# Precision_LPC.net
KiCad netlist of a schematic drawn in EAGLE
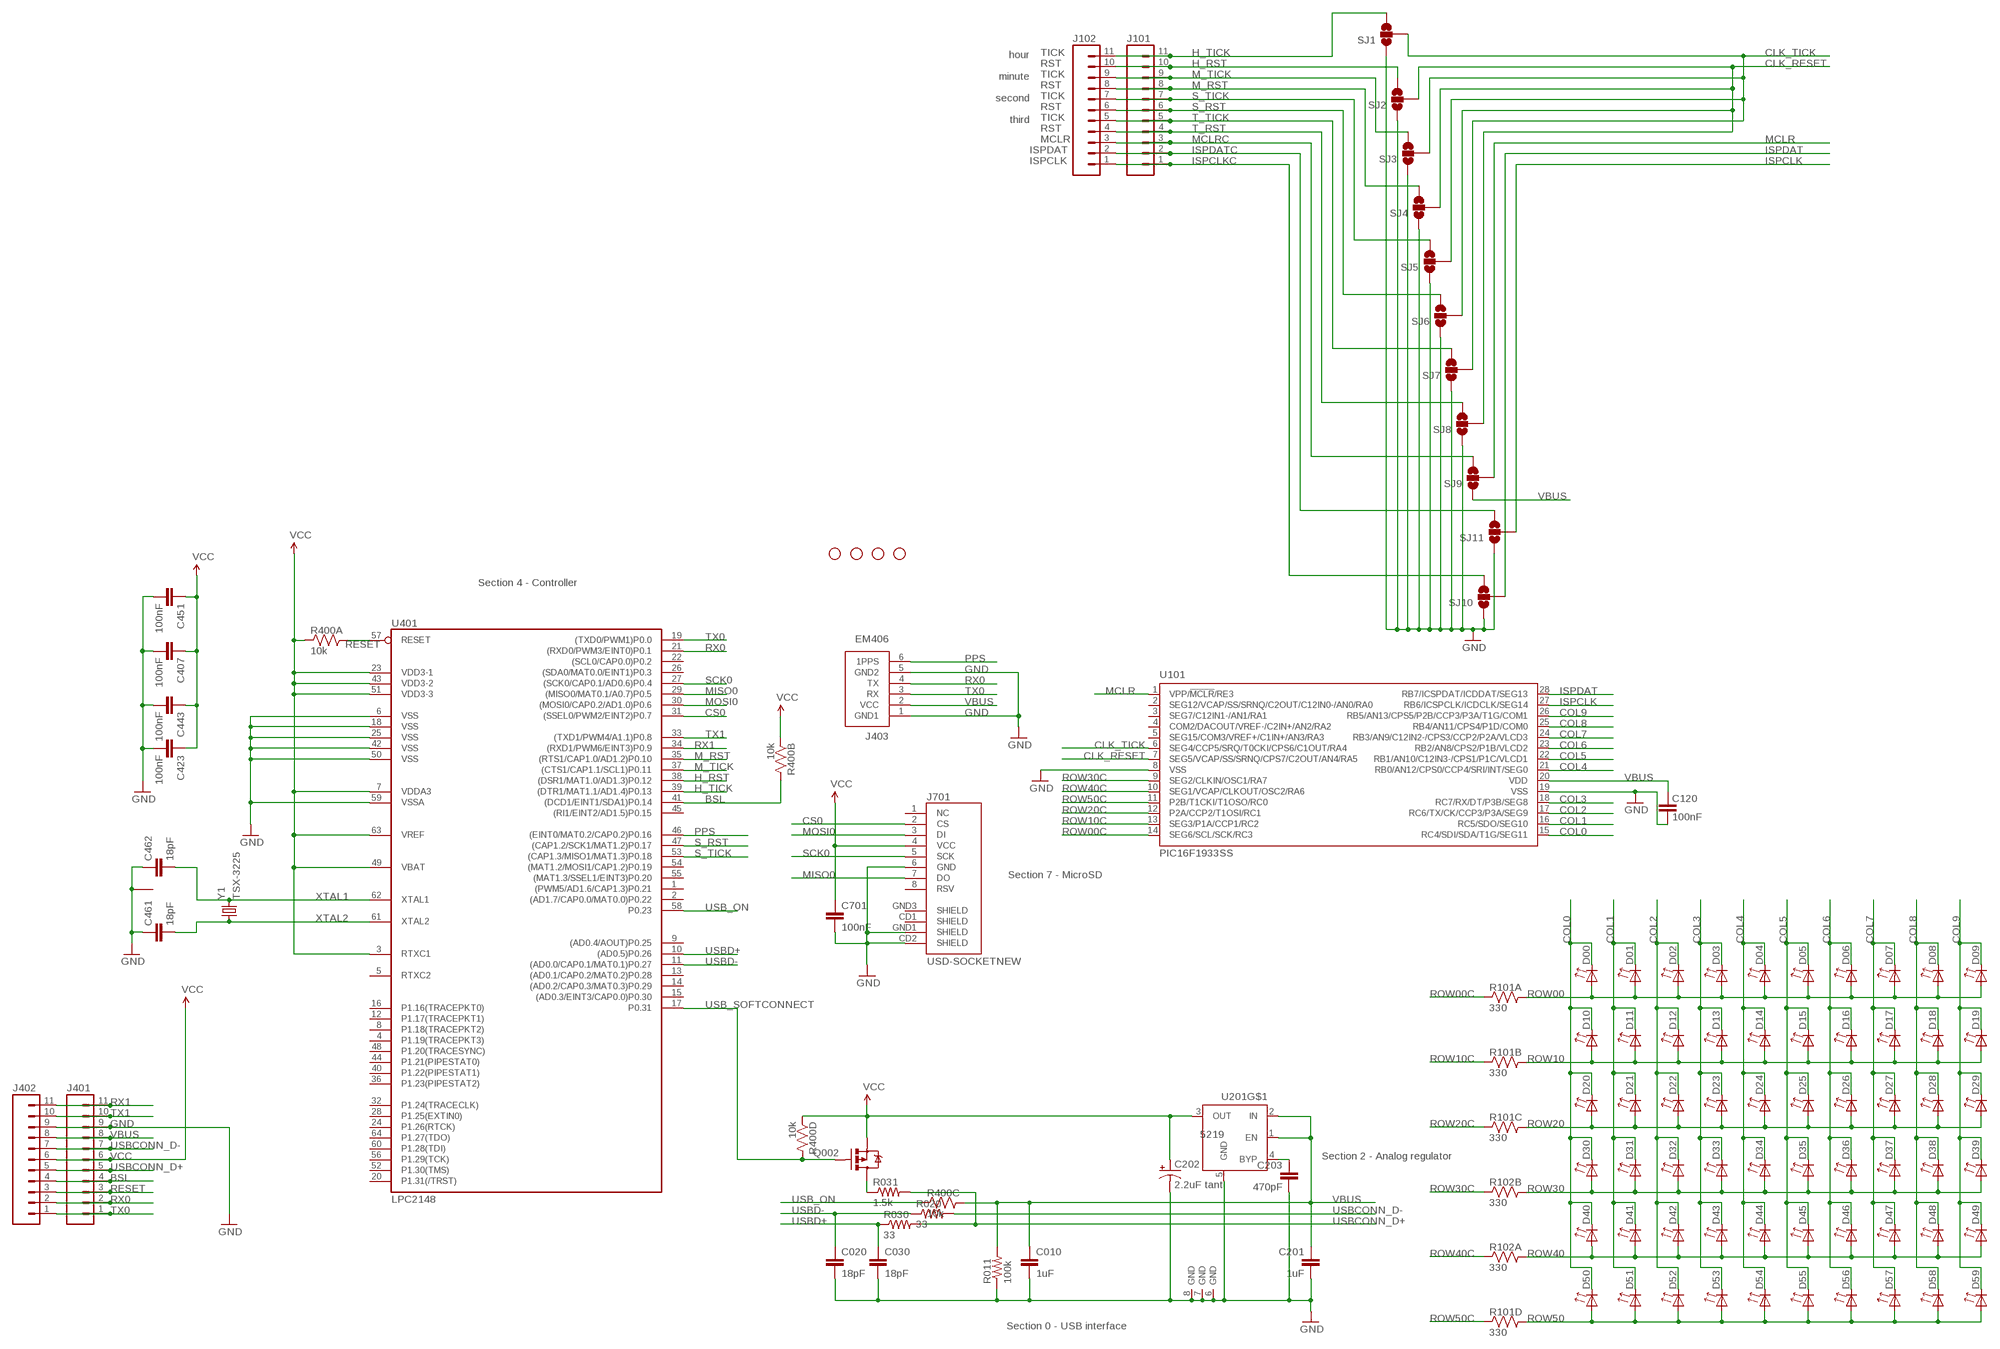
[diagram p0: schematic, sheet 1]

(export (version "E")
  (design (tool "Eeschema 10.0.6"))
  (components
    (comp (ref "C010")
      (value "1uF")
      (footprint "eagle-import:0402-CAP")
      (libsource (lib "eagle-import") (part "CAP0402-CAP"))
    )
    (comp (ref "C020")
      (value "18pF")
      (footprint "eagle-import:0402-CAP")
      (libsource (lib "eagle-import") (part "CAP0402-CAP"))
    )
    (comp (ref "C030")
      (value "18pF")
      (footprint "eagle-import:0402-CAP")
      (libsource (lib "eagle-import") (part "CAP0402-CAP"))
    )
    (comp (ref "C120")
      (value "100nF")
      (footprint "eagle-import:0402-CAP")
      (libsource (lib "eagle-import") (part "CAP0402-CAP"))
    )
    (comp (ref "C201")
      (value "1uF")
      (footprint "eagle-import:0402-CAP")
      (libsource (lib "eagle-import") (part "CAP0402-CAP"))
    )
    (comp (ref "C202")
      (value "2.2uF tant")
      (footprint "eagle-import:EIA3216")
      (libsource (lib "eagle-import") (part "CAP_POL1206"))
    )
    (comp (ref "C203")
      (value "470pF")
      (footprint "eagle-import:0402-CAP")
      (libsource (lib "eagle-import") (part "CAP0402-CAP"))
    )
    (comp (ref "C407")
      (value "100nF")
      (footprint "eagle-import:0402-CAP")
      (libsource (lib "eagle-import") (part "CAP0402-CAP"))
    )
    (comp (ref "C423")
      (value "100nF")
      (footprint "eagle-import:0402-CAP")
      (libsource (lib "eagle-import") (part "CAP0402-CAP"))
    )
    (comp (ref "C443")
      (value "100nF")
      (footprint "eagle-import:0402-CAP")
      (libsource (lib "eagle-import") (part "CAP0402-CAP"))
    )
    (comp (ref "C451")
      (value "100nF")
      (footprint "eagle-import:0402-CAP")
      (libsource (lib "eagle-import") (part "CAP0402-CAP"))
    )
    (comp (ref "C461")
      (value "18pF")
      (footprint "eagle-import:0402-CAP")
      (libsource (lib "eagle-import") (part "CAP0402-CAP"))
    )
    (comp (ref "C462")
      (value "18pF")
      (footprint "eagle-import:0402-CAP")
      (libsource (lib "eagle-import") (part "CAP0402-CAP"))
    )
    (comp (ref "C701")
      (value "100nF")
      (footprint "eagle-import:0402-CAP")
      (libsource (lib "eagle-import") (part "CAP0402-CAP"))
    )
    (comp (ref "D00")
      (value "LED0603_SIDE")
      (footprint "eagle-import:LED0603_SIDE")
      (libsource (lib "eagle-import") (part "LED0603_SIDE"))
    )
    (comp (ref "D01")
      (value "LED0603_SIDE")
      (footprint "eagle-import:LED0603_SIDE")
      (libsource (lib "eagle-import") (part "LED0603_SIDE"))
    )
    (comp (ref "D02")
      (value "LED0603_SIDE")
      (footprint "eagle-import:LED0603_SIDE")
      (libsource (lib "eagle-import") (part "LED0603_SIDE"))
    )
    (comp (ref "D03")
      (value "LED0603_SIDE")
      (footprint "eagle-import:LED0603_SIDE")
      (libsource (lib "eagle-import") (part "LED0603_SIDE"))
    )
    (comp (ref "D04")
      (value "LED0603_SIDE")
      (footprint "eagle-import:LED0603_SIDE")
      (libsource (lib "eagle-import") (part "LED0603_SIDE"))
    )
    (comp (ref "D05")
      (value "LED0603_SIDE")
      (footprint "eagle-import:LED0603_SIDE")
      (libsource (lib "eagle-import") (part "LED0603_SIDE"))
    )
    (comp (ref "D06")
      (value "LED0603_SIDE")
      (footprint "eagle-import:LED0603_SIDE")
      (libsource (lib "eagle-import") (part "LED0603_SIDE"))
    )
    (comp (ref "D07")
      (value "LED0603_SIDE")
      (footprint "eagle-import:LED0603_SIDE")
      (libsource (lib "eagle-import") (part "LED0603_SIDE"))
    )
    (comp (ref "D08")
      (value "LED0603_SIDE")
      (footprint "eagle-import:LED0603_SIDE")
      (libsource (lib "eagle-import") (part "LED0603_SIDE"))
    )
    (comp (ref "D09")
      (value "LED0603_SIDE")
      (footprint "eagle-import:LED0603_SIDE")
      (libsource (lib "eagle-import") (part "LED0603_SIDE"))
    )
    (comp (ref "D10")
      (value "LED0603_SIDE")
      (footprint "eagle-import:LED0603_SIDE")
      (libsource (lib "eagle-import") (part "LED0603_SIDE"))
    )
    (comp (ref "D11")
      (value "LED0603_SIDE")
      (footprint "eagle-import:LED0603_SIDE")
      (libsource (lib "eagle-import") (part "LED0603_SIDE"))
    )
    (comp (ref "D12")
      (value "LED0603_SIDE")
      (footprint "eagle-import:LED0603_SIDE")
      (libsource (lib "eagle-import") (part "LED0603_SIDE"))
    )
    (comp (ref "D13")
      (value "LED0603_SIDE")
      (footprint "eagle-import:LED0603_SIDE")
      (libsource (lib "eagle-import") (part "LED0603_SIDE"))
    )
    (comp (ref "D14")
      (value "LED0603_SIDE")
      (footprint "eagle-import:LED0603_SIDE")
      (libsource (lib "eagle-import") (part "LED0603_SIDE"))
    )
    (comp (ref "D15")
      (value "LED0603_SIDE")
      (footprint "eagle-import:LED0603_SIDE")
      (libsource (lib "eagle-import") (part "LED0603_SIDE"))
    )
    (comp (ref "D16")
      (value "LED0603_SIDE")
      (footprint "eagle-import:LED0603_SIDE")
      (libsource (lib "eagle-import") (part "LED0603_SIDE"))
    )
    (comp (ref "D17")
      (value "LED0603_SIDE")
      (footprint "eagle-import:LED0603_SIDE")
      (libsource (lib "eagle-import") (part "LED0603_SIDE"))
    )
    (comp (ref "D18")
      (value "LED0603_SIDE")
      (footprint "eagle-import:LED0603_SIDE")
      (libsource (lib "eagle-import") (part "LED0603_SIDE"))
    )
    (comp (ref "D19")
      (value "LED0603_SIDE")
      (footprint "eagle-import:LED0603_SIDE")
      (libsource (lib "eagle-import") (part "LED0603_SIDE"))
    )
    (comp (ref "D20")
      (value "LED0603_SIDE")
      (footprint "eagle-import:LED0603_SIDE")
      (libsource (lib "eagle-import") (part "LED0603_SIDE"))
    )
    (comp (ref "D21")
      (value "LED0603_SIDE")
      (footprint "eagle-import:LED0603_SIDE")
      (libsource (lib "eagle-import") (part "LED0603_SIDE"))
    )
    (comp (ref "D22")
      (value "LED0603_SIDE")
      (footprint "eagle-import:LED0603_SIDE")
      (libsource (lib "eagle-import") (part "LED0603_SIDE"))
    )
    (comp (ref "D23")
      (value "LED0603_SIDE")
      (footprint "eagle-import:LED0603_SIDE")
      (libsource (lib "eagle-import") (part "LED0603_SIDE"))
    )
    (comp (ref "D24")
      (value "LED0603_SIDE")
      (footprint "eagle-import:LED0603_SIDE")
      (libsource (lib "eagle-import") (part "LED0603_SIDE"))
    )
    (comp (ref "D25")
      (value "LED0603_SIDE")
      (footprint "eagle-import:LED0603_SIDE")
      (libsource (lib "eagle-import") (part "LED0603_SIDE"))
    )
    (comp (ref "D26")
      (value "LED0603_SIDE")
      (footprint "eagle-import:LED0603_SIDE")
      (libsource (lib "eagle-import") (part "LED0603_SIDE"))
    )
    (comp (ref "D27")
      (value "LED0603_SIDE")
      (footprint "eagle-import:LED0603_SIDE")
      (libsource (lib "eagle-import") (part "LED0603_SIDE"))
    )
    (comp (ref "D28")
      (value "LED0603_SIDE")
      (footprint "eagle-import:LED0603_SIDE")
      (libsource (lib "eagle-import") (part "LED0603_SIDE"))
    )
    (comp (ref "D29")
      (value "LED0603_SIDE")
      (footprint "eagle-import:LED0603_SIDE")
      (libsource (lib "eagle-import") (part "LED0603_SIDE"))
    )
    (comp (ref "D30")
      (value "LED0603_SIDE")
      (footprint "eagle-import:LED0603_SIDE")
      (libsource (lib "eagle-import") (part "LED0603_SIDE"))
    )
    (comp (ref "D31")
      (value "LED0603_SIDE")
      (footprint "eagle-import:LED0603_SIDE")
      (libsource (lib "eagle-import") (part "LED0603_SIDE"))
    )
    (comp (ref "D32")
      (value "LED0603_SIDE")
      (footprint "eagle-import:LED0603_SIDE")
      (libsource (lib "eagle-import") (part "LED0603_SIDE"))
    )
    (comp (ref "D33")
      (value "LED0603_SIDE")
      (footprint "eagle-import:LED0603_SIDE")
      (libsource (lib "eagle-import") (part "LED0603_SIDE"))
    )
    (comp (ref "D34")
      (value "LED0603_SIDE")
      (footprint "eagle-import:LED0603_SIDE")
      (libsource (lib "eagle-import") (part "LED0603_SIDE"))
    )
    (comp (ref "D35")
      (value "LED0603_SIDE")
      (footprint "eagle-import:LED0603_SIDE")
      (libsource (lib "eagle-import") (part "LED0603_SIDE"))
    )
    (comp (ref "D36")
      (value "LED0603_SIDE")
      (footprint "eagle-import:LED0603_SIDE")
      (libsource (lib "eagle-import") (part "LED0603_SIDE"))
    )
    (comp (ref "D37")
      (value "LED0603_SIDE")
      (footprint "eagle-import:LED0603_SIDE")
      (libsource (lib "eagle-import") (part "LED0603_SIDE"))
    )
    (comp (ref "D38")
      (value "LED0603_SIDE")
      (footprint "eagle-import:LED0603_SIDE")
      (libsource (lib "eagle-import") (part "LED0603_SIDE"))
    )
    (comp (ref "D39")
      (value "LED0603_SIDE")
      (footprint "eagle-import:LED0603_SIDE")
      (libsource (lib "eagle-import") (part "LED0603_SIDE"))
    )
    (comp (ref "D40")
      (value "LED0603_SIDE")
      (footprint "eagle-import:LED0603_SIDE")
      (libsource (lib "eagle-import") (part "LED0603_SIDE"))
    )
    (comp (ref "D41")
      (value "LED0603_SIDE")
      (footprint "eagle-import:LED0603_SIDE")
      (libsource (lib "eagle-import") (part "LED0603_SIDE"))
    )
    (comp (ref "D42")
      (value "LED0603_SIDE")
      (footprint "eagle-import:LED0603_SIDE")
      (libsource (lib "eagle-import") (part "LED0603_SIDE"))
    )
    (comp (ref "D43")
      (value "LED0603_SIDE")
      (footprint "eagle-import:LED0603_SIDE")
      (libsource (lib "eagle-import") (part "LED0603_SIDE"))
    )
    (comp (ref "D44")
      (value "LED0603_SIDE")
      (footprint "eagle-import:LED0603_SIDE")
      (libsource (lib "eagle-import") (part "LED0603_SIDE"))
    )
    (comp (ref "D45")
      (value "LED0603_SIDE")
      (footprint "eagle-import:LED0603_SIDE")
      (libsource (lib "eagle-import") (part "LED0603_SIDE"))
    )
    (comp (ref "D46")
      (value "LED0603_SIDE")
      (footprint "eagle-import:LED0603_SIDE")
      (libsource (lib "eagle-import") (part "LED0603_SIDE"))
    )
    (comp (ref "D47")
      (value "LED0603_SIDE")
      (footprint "eagle-import:LED0603_SIDE")
      (libsource (lib "eagle-import") (part "LED0603_SIDE"))
    )
    (comp (ref "D48")
      (value "LED0603_SIDE")
      (footprint "eagle-import:LED0603_SIDE")
      (libsource (lib "eagle-import") (part "LED0603_SIDE"))
    )
    (comp (ref "D49")
      (value "LED0603_SIDE")
      (footprint "eagle-import:LED0603_SIDE")
      (libsource (lib "eagle-import") (part "LED0603_SIDE"))
    )
    (comp (ref "D50")
      (value "LED0603_SIDE")
      (footprint "eagle-import:LED0603_SIDE")
      (libsource (lib "eagle-import") (part "LED0603_SIDE"))
    )
    (comp (ref "D51")
      (value "LED0603_SIDE")
      (footprint "eagle-import:LED0603_SIDE")
      (libsource (lib "eagle-import") (part "LED0603_SIDE"))
    )
    (comp (ref "D52")
      (value "LED0603_SIDE")
      (footprint "eagle-import:LED0603_SIDE")
      (libsource (lib "eagle-import") (part "LED0603_SIDE"))
    )
    (comp (ref "D53")
      (value "LED0603_SIDE")
      (footprint "eagle-import:LED0603_SIDE")
      (libsource (lib "eagle-import") (part "LED0603_SIDE"))
    )
    (comp (ref "D54")
      (value "LED0603_SIDE")
      (footprint "eagle-import:LED0603_SIDE")
      (libsource (lib "eagle-import") (part "LED0603_SIDE"))
    )
    (comp (ref "D55")
      (value "LED0603_SIDE")
      (footprint "eagle-import:LED0603_SIDE")
      (libsource (lib "eagle-import") (part "LED0603_SIDE"))
    )
    (comp (ref "D56")
      (value "LED0603_SIDE")
      (footprint "eagle-import:LED0603_SIDE")
      (libsource (lib "eagle-import") (part "LED0603_SIDE"))
    )
    (comp (ref "D57")
      (value "LED0603_SIDE")
      (footprint "eagle-import:LED0603_SIDE")
      (libsource (lib "eagle-import") (part "LED0603_SIDE"))
    )
    (comp (ref "D58")
      (value "LED0603_SIDE")
      (footprint "eagle-import:LED0603_SIDE")
      (libsource (lib "eagle-import") (part "LED0603_SIDE"))
    )
    (comp (ref "D59")
      (value "LED0603_SIDE")
      (footprint "eagle-import:LED0603_SIDE")
      (libsource (lib "eagle-import") (part "LED0603_SIDE"))
    )
    (comp (ref "J101")
      (value "M11PTH")
      (footprint "eagle-import:1X11")
      (libsource (lib "eagle-import") (part "M11PTH"))
    )
    (comp (ref "J102")
      (value "M11PTH")
      (footprint "eagle-import:1X11")
      (libsource (lib "eagle-import") (part "M11PTH"))
    )
    (comp (ref "J401")
      (value "M11PTH")
      (footprint "eagle-import:1X11")
      (libsource (lib "eagle-import") (part "M11PTH"))
    )
    (comp (ref "J402")
      (value "M11PTH")
      (footprint "eagle-import:1X11")
      (libsource (lib "eagle-import") (part "M11PTH"))
    )
    (comp (ref "J403")
      (value "EM406")
      (footprint "eagle-import:EM406@1")
      (libsource (lib "eagle-import") (part "EM406"))
    )
    (comp (ref "J701")
      (value "USD-SOCKETNEW")
      (footprint "eagle-import:MICRO-SD-SOCKET-PP")
      (libsource (lib "eagle-import") (part "USD-SOCKETNEW"))
    )
    (comp (ref "JP3")
      (value "STAND-OFF")
      (footprint "eagle-import:STAND-OFF")
      (libsource (lib "eagle-import") (part "STAND-OFF"))
    )
    (comp (ref "JP4")
      (value "STAND-OFF")
      (footprint "eagle-import:STAND-OFF")
      (libsource (lib "eagle-import") (part "STAND-OFF"))
    )
    (comp (ref "JP5")
      (value "STAND-OFF")
      (footprint "eagle-import:STAND-OFF")
      (libsource (lib "eagle-import") (part "STAND-OFF"))
    )
    (comp (ref "JP6")
      (value "STAND-OFF")
      (footprint "eagle-import:STAND-OFF")
      (libsource (lib "eagle-import") (part "STAND-OFF"))
    )
    (comp (ref "Q002")
      (value "PMOS")
      (footprint "eagle-import:SOT23-3")
      (libsource (lib "eagle-import") (part "MOSFET-PCHANNELSMD"))
    )
    (comp (ref "R011")
      (value "100k")
      (footprint "eagle-import:0402-RES")
      (libsource (lib "eagle-import") (part "RESISTOR0402-RES"))
    )
    (comp (ref "R020")
      (value "33")
      (footprint "eagle-import:0402-RES")
      (libsource (lib "eagle-import") (part "RESISTOR0402-RES"))
    )
    (comp (ref "R030")
      (value "33")
      (footprint "eagle-import:0402-RES")
      (libsource (lib "eagle-import") (part "RESISTOR0402-RES"))
    )
    (comp (ref "R031")
      (value "1.5k")
      (footprint "eagle-import:0402-RES")
      (libsource (lib "eagle-import") (part "RESISTOR0402-RES"))
    )
    (comp (ref "R101")
      (value "330")
      (footprint "eagle-import:CRA04")
      (libsource (lib "eagle-import") (part "RP404"))
    )
    (comp (ref "R102")
      (value "330")
      (footprint "eagle-import:CRA04")
      (libsource (lib "eagle-import") (part "RP404"))
    )
    (comp (ref "R400")
      (value "10k")
      (footprint "eagle-import:CRA04")
      (libsource (lib "eagle-import") (part "RP404"))
    )
    (comp (ref "SJ1")
      (value "SOLDERJUMPER_2WAYS")
      (footprint "eagle-import:SJ_3")
      (libsource (lib "eagle-import") (part "SOLDERJUMPER_2WAYS"))
    )
    (comp (ref "SJ2")
      (value "SOLDERJUMPER_2WAYS")
      (footprint "eagle-import:SJ_3")
      (libsource (lib "eagle-import") (part "SOLDERJUMPER_2WAYS"))
    )
    (comp (ref "SJ3")
      (value "SOLDERJUMPER_2WAYS")
      (footprint "eagle-import:SJ_3")
      (libsource (lib "eagle-import") (part "SOLDERJUMPER_2WAYS"))
    )
    (comp (ref "SJ4")
      (value "SOLDERJUMPER_2WAYS")
      (footprint "eagle-import:SJ_3")
      (libsource (lib "eagle-import") (part "SOLDERJUMPER_2WAYS"))
    )
    (comp (ref "SJ5")
      (value "SOLDERJUMPER_2WAYS")
      (footprint "eagle-import:SJ_3")
      (libsource (lib "eagle-import") (part "SOLDERJUMPER_2WAYS"))
    )
    (comp (ref "SJ6")
      (value "SOLDERJUMPER_2WAYS")
      (footprint "eagle-import:SJ_3")
      (libsource (lib "eagle-import") (part "SOLDERJUMPER_2WAYS"))
    )
    (comp (ref "SJ7")
      (value "SOLDERJUMPER_2WAYS")
      (footprint "eagle-import:SJ_3")
      (libsource (lib "eagle-import") (part "SOLDERJUMPER_2WAYS"))
    )
    (comp (ref "SJ8")
      (value "SOLDERJUMPER_2WAYS")
      (footprint "eagle-import:SJ_3")
      (libsource (lib "eagle-import") (part "SOLDERJUMPER_2WAYS"))
    )
    (comp (ref "SJ9")
      (value "SOLDERJUMPER_2WAYS")
      (footprint "eagle-import:SJ_3")
      (libsource (lib "eagle-import") (part "SOLDERJUMPER_2WAYS"))
    )
    (comp (ref "SJ10")
      (value "SOLDERJUMPER_2WAYS")
      (footprint "eagle-import:SJ_3")
      (libsource (lib "eagle-import") (part "SOLDERJUMPER_2WAYS"))
    )
    (comp (ref "SJ11")
      (value "SOLDERJUMPER_2WAYS")
      (footprint "eagle-import:SJ_3")
      (libsource (lib "eagle-import") (part "SOLDERJUMPER_2WAYS"))
    )
    (comp (ref "U101")
      (value "PIC16F1933SS")
      (footprint "eagle-import:SSOP28")
      (fields (field (name "MPN") "PIC16F1933T-I/SS"))
      (libsource (lib "eagle-import") (part "PIC16F19SS33"))
    )
    (comp (ref "U201")
      (value "5219")
      (footprint "eagle-import:MSOP08")
      (libsource (lib "eagle-import") (part "MIC5219FMM"))
    )
    (comp (ref "U401")
      (value "LPC2148")
      (footprint "eagle-import:SQFP-S-10X10-64")
      (libsource (lib "eagle-import") (part "LPC213X"))
    )
    (comp (ref "Y1")
      (value "TSX-3225")
      (footprint "eagle-import:CRYSTAL_SMD")
      (libsource (lib "eagle-import") (part "TSX-3225"))
    )
  )
  (nets
    (net (code "1") (name "/BSL") (class "Default")
      (node (ref "J401") (pin "4") (pinfunction "4_4") (pintype "passive"))
      (node (ref "J402") (pin "4") (pinfunction "4_4") (pintype "passive"))
      (node (ref "R400") (pin "7") (pinfunction "2_7") (pintype "passive"))
      (node (ref "U401") (pin "41") (pinfunction "(DCD1/EINT1/SDA1)P0.14_41") (pintype "bidirectional"))
    )
    (net (code "2") (name "/CLK_RESET") (class "Default")
      (node (ref "SJ2") (pin "2") (pinfunction "2_2") (pintype "passive"))
      (node (ref "SJ4") (pin "2") (pinfunction "2_2") (pintype "passive"))
      (node (ref "SJ6") (pin "2") (pinfunction "2_2") (pintype "passive"))
      (node (ref "SJ8") (pin "2") (pinfunction "2_2") (pintype "passive"))
      (node (ref "U101") (pin "7") (pinfunction "SEG5/VCAP/SS/SRNQ/CPS7/C2OUT/AN4/RA5_7") (pintype "bidirectional"))
    )
    (net (code "3") (name "/CLK_TICK") (class "Default")
      (node (ref "SJ1") (pin "2") (pinfunction "2_2") (pintype "passive"))
      (node (ref "SJ3") (pin "2") (pinfunction "2_2") (pintype "passive"))
      (node (ref "SJ5") (pin "2") (pinfunction "2_2") (pintype "passive"))
      (node (ref "SJ7") (pin "2") (pinfunction "2_2") (pintype "passive"))
      (node (ref "U101") (pin "6") (pinfunction "SEG4/CCP5/SRQ/T0CKI/CPS6/C1OUT/RA4_6") (pintype "bidirectional"))
    )
    (net (code "4") (name "/COL0") (class "Default")
      (node (ref "D00") (pin "C") (pinfunction "C_C") (pintype "passive"))
      (node (ref "D10") (pin "C") (pinfunction "C_C") (pintype "passive"))
      (node (ref "D20") (pin "C") (pinfunction "C_C") (pintype "passive"))
      (node (ref "D30") (pin "C") (pinfunction "C_C") (pintype "passive"))
      (node (ref "D40") (pin "C") (pinfunction "C_C") (pintype "passive"))
      (node (ref "D50") (pin "C") (pinfunction "C_C") (pintype "passive"))
      (node (ref "U101") (pin "15") (pinfunction "RC4/SDI/SDA/T1G/SEG11_15") (pintype "bidirectional"))
    )
    (net (code "5") (name "/COL1") (class "Default")
      (node (ref "D01") (pin "C") (pinfunction "C_C") (pintype "passive"))
      (node (ref "D11") (pin "C") (pinfunction "C_C") (pintype "passive"))
      (node (ref "D21") (pin "C") (pinfunction "C_C") (pintype "passive"))
      (node (ref "D31") (pin "C") (pinfunction "C_C") (pintype "passive"))
      (node (ref "D41") (pin "C") (pinfunction "C_C") (pintype "passive"))
      (node (ref "D51") (pin "C") (pinfunction "C_C") (pintype "passive"))
      (node (ref "U101") (pin "16") (pinfunction "RC5/SDO/SEG10_16") (pintype "bidirectional"))
    )
    (net (code "6") (name "/COL2") (class "Default")
      (node (ref "D02") (pin "C") (pinfunction "C_C") (pintype "passive"))
      (node (ref "D12") (pin "C") (pinfunction "C_C") (pintype "passive"))
      (node (ref "D22") (pin "C") (pinfunction "C_C") (pintype "passive"))
      (node (ref "D32") (pin "C") (pinfunction "C_C") (pintype "passive"))
      (node (ref "D42") (pin "C") (pinfunction "C_C") (pintype "passive"))
      (node (ref "D52") (pin "C") (pinfunction "C_C") (pintype "passive"))
      (node (ref "U101") (pin "17") (pinfunction "RC6/TX/CK/CCP3/P3A/SEG9_17") (pintype "bidirectional"))
    )
    (net (code "7") (name "/COL3") (class "Default")
      (node (ref "D03") (pin "C") (pinfunction "C_C") (pintype "passive"))
      (node (ref "D13") (pin "C") (pinfunction "C_C") (pintype "passive"))
      (node (ref "D23") (pin "C") (pinfunction "C_C") (pintype "passive"))
      (node (ref "D33") (pin "C") (pinfunction "C_C") (pintype "passive"))
      (node (ref "D43") (pin "C") (pinfunction "C_C") (pintype "passive"))
      (node (ref "D53") (pin "C") (pinfunction "C_C") (pintype "passive"))
      (node (ref "U101") (pin "18") (pinfunction "RC7/RX/DT/P3B/SEG8_18") (pintype "bidirectional"))
    )
    (net (code "8") (name "/COL4") (class "Default")
      (node (ref "D04") (pin "C") (pinfunction "C_C") (pintype "passive"))
      (node (ref "D14") (pin "C") (pinfunction "C_C") (pintype "passive"))
      (node (ref "D24") (pin "C") (pinfunction "C_C") (pintype "passive"))
      (node (ref "D34") (pin "C") (pinfunction "C_C") (pintype "passive"))
      (node (ref "D44") (pin "C") (pinfunction "C_C") (pintype "passive"))
      (node (ref "D54") (pin "C") (pinfunction "C_C") (pintype "passive"))
      (node (ref "U101") (pin "21") (pinfunction "RB0/AN12/CPS0/CCP4/SRI/INT/SEG0_21") (pintype "bidirectional"))
    )
    (net (code "9") (name "/COL5") (class "Default")
      (node (ref "D05") (pin "C") (pinfunction "C_C") (pintype "passive"))
      (node (ref "D15") (pin "C") (pinfunction "C_C") (pintype "passive"))
      (node (ref "D25") (pin "C") (pinfunction "C_C") (pintype "passive"))
      (node (ref "D35") (pin "C") (pinfunction "C_C") (pintype "passive"))
      (node (ref "D45") (pin "C") (pinfunction "C_C") (pintype "passive"))
      (node (ref "D55") (pin "C") (pinfunction "C_C") (pintype "passive"))
      (node (ref "U101") (pin "22") (pinfunction "RB1/AN10/C12IN3-/CPS1/P1C/VLCD1_22") (pintype "bidirectional"))
    )
    (net (code "10") (name "/COL6") (class "Default")
      (node (ref "D06") (pin "C") (pinfunction "C_C") (pintype "passive"))
      (node (ref "D16") (pin "C") (pinfunction "C_C") (pintype "passive"))
      (node (ref "D26") (pin "C") (pinfunction "C_C") (pintype "passive"))
      (node (ref "D36") (pin "C") (pinfunction "C_C") (pintype "passive"))
      (node (ref "D46") (pin "C") (pinfunction "C_C") (pintype "passive"))
      (node (ref "D56") (pin "C") (pinfunction "C_C") (pintype "passive"))
      (node (ref "U101") (pin "23") (pinfunction "RB2/AN8/CPS2/P1B/VLCD2_23") (pintype "bidirectional"))
    )
    (net (code "11") (name "/COL7") (class "Default")
      (node (ref "D07") (pin "C") (pinfunction "C_C") (pintype "passive"))
      (node (ref "D17") (pin "C") (pinfunction "C_C") (pintype "passive"))
      (node (ref "D27") (pin "C") (pinfunction "C_C") (pintype "passive"))
      (node (ref "D37") (pin "C") (pinfunction "C_C") (pintype "passive"))
      (node (ref "D47") (pin "C") (pinfunction "C_C") (pintype "passive"))
      (node (ref "D57") (pin "C") (pinfunction "C_C") (pintype "passive"))
      (node (ref "U101") (pin "24") (pinfunction "RB3/AN9/C12IN2-/CPS3/CCP2/P2A/VLCD3_24") (pintype "bidirectional"))
    )
    (net (code "12") (name "/COL8") (class "Default")
      (node (ref "D08") (pin "C") (pinfunction "C_C") (pintype "passive"))
      (node (ref "D18") (pin "C") (pinfunction "C_C") (pintype "passive"))
      (node (ref "D28") (pin "C") (pinfunction "C_C") (pintype "passive"))
      (node (ref "D38") (pin "C") (pinfunction "C_C") (pintype "passive"))
      (node (ref "D48") (pin "C") (pinfunction "C_C") (pintype "passive"))
      (node (ref "D58") (pin "C") (pinfunction "C_C") (pintype "passive"))
      (node (ref "U101") (pin "25") (pinfunction "RB4/AN11/CPS4/P1D/COM0_25") (pintype "bidirectional"))
    )
    (net (code "13") (name "/COL9") (class "Default")
      (node (ref "D09") (pin "C") (pinfunction "C_C") (pintype "passive"))
      (node (ref "D19") (pin "C") (pinfunction "C_C") (pintype "passive"))
      (node (ref "D29") (pin "C") (pinfunction "C_C") (pintype "passive"))
      (node (ref "D39") (pin "C") (pinfunction "C_C") (pintype "passive"))
      (node (ref "D49") (pin "C") (pinfunction "C_C") (pintype "passive"))
      (node (ref "D59") (pin "C") (pinfunction "C_C") (pintype "passive"))
      (node (ref "U101") (pin "26") (pinfunction "RB5/AN13/CPS5/P2B/CCP3/P3A/T1G/COM1_26") (pintype "bidirectional"))
    )
    (net (code "14") (name "/CS0") (class "Default")
      (node (ref "J701") (pin "2") (pinfunction "CS_2") (pintype "bidirectional"))
      (node (ref "U401") (pin "31") (pinfunction "(SSEL0/PWM2/EINT2)P0.7_31") (pintype "bidirectional"))
    )
    (net (code "15") (name "/H_RST") (class "Default")
      (node (ref "J101") (pin "10") (pinfunction "10_10") (pintype "passive"))
      (node (ref "J102") (pin "10") (pinfunction "10_10") (pintype "passive"))
      (node (ref "SJ2") (pin "3") (pinfunction "3_3") (pintype "passive"))
      (node (ref "U401") (pin "38") (pinfunction "(DSR1/MAT1.0/AD1.3)P0.12_38") (pintype "bidirectional"))
    )
    (net (code "16") (name "/H_TICK") (class "Default")
      (node (ref "J101") (pin "11") (pinfunction "11_11") (pintype "passive"))
      (node (ref "J102") (pin "11") (pinfunction "11_11") (pintype "passive"))
      (node (ref "SJ1") (pin "3") (pinfunction "3_3") (pintype "passive"))
      (node (ref "U401") (pin "39") (pinfunction "(DTR1/MAT1.1/AD1.4)P0.13_39") (pintype "bidirectional"))
    )
    (net (code "17") (name "/ISPCLK") (class "Default")
      (node (ref "SJ11") (pin "2") (pinfunction "2_2") (pintype "passive"))
      (node (ref "U101") (pin "27") (pinfunction "RB6/ICSPCLK/ICDCLK/SEG14_27") (pintype "bidirectional"))
    )
    (net (code "18") (name "/ISPCLKC") (class "Default")
      (node (ref "J101") (pin "2") (pinfunction "2_2") (pintype "passive"))
      (node (ref "J102") (pin "2") (pinfunction "2_2") (pintype "passive"))
      (node (ref "SJ11") (pin "3") (pinfunction "3_3") (pintype "passive"))
    )
    (net (code "19") (name "/ISPDAT") (class "Default")
      (node (ref "SJ10") (pin "2") (pinfunction "2_2") (pintype "passive"))
      (node (ref "U101") (pin "28") (pinfunction "RB7/ICSPDAT/ICDDAT/SEG13_28") (pintype "bidirectional"))
    )
    (net (code "20") (name "/ISPDATC") (class "Default")
      (node (ref "J101") (pin "1") (pinfunction "1_1") (pintype "passive"))
      (node (ref "J102") (pin "1") (pinfunction "1_1") (pintype "passive"))
      (node (ref "SJ10") (pin "3") (pinfunction "3_3") (pintype "passive"))
    )
    (net (code "21") (name "/MCLR") (class "Default")
      (node (ref "SJ9") (pin "2") (pinfunction "2_2") (pintype "passive"))
      (node (ref "U101") (pin "1") (pinfunction "VPP/~{MCLR}/RE3_1") (pintype "input"))
    )
    (net (code "22") (name "/MCLRC") (class "Default")
      (node (ref "J101") (pin "3") (pinfunction "3_3") (pintype "passive"))
      (node (ref "J102") (pin "3") (pinfunction "3_3") (pintype "passive"))
      (node (ref "SJ9") (pin "3") (pinfunction "3_3") (pintype "passive"))
    )
    (net (code "23") (name "/MISO0") (class "Default")
      (node (ref "J701") (pin "7") (pinfunction "DO_7") (pintype "bidirectional"))
      (node (ref "U401") (pin "29") (pinfunction "(MISO0/MAT0.1/A0.7)P0.5_29") (pintype "bidirectional"))
    )
    (net (code "24") (name "/MOSI0") (class "Default")
      (node (ref "J701") (pin "3") (pinfunction "DI_3") (pintype "bidirectional"))
      (node (ref "U401") (pin "30") (pinfunction "(MOSI0/CAP0.2/AD1.0)P0.6_30") (pintype "bidirectional"))
    )
    (net (code "25") (name "/M_RST") (class "Default")
      (node (ref "J101") (pin "8") (pinfunction "8_8") (pintype "passive"))
      (node (ref "J102") (pin "8") (pinfunction "8_8") (pintype "passive"))
      (node (ref "SJ4") (pin "3") (pinfunction "3_3") (pintype "passive"))
      (node (ref "U401") (pin "35") (pinfunction "(RTS1/CAP1.0/AD1.2)P0.10_35") (pintype "bidirectional"))
    )
    (net (code "26") (name "/M_TICK") (class "Default")
      (node (ref "J101") (pin "9") (pinfunction "9_9") (pintype "passive"))
      (node (ref "J102") (pin "9") (pinfunction "9_9") (pintype "passive"))
      (node (ref "SJ3") (pin "3") (pinfunction "3_3") (pintype "passive"))
      (node (ref "U401") (pin "37") (pinfunction "(CTS1/CAP1.1/SCL1)P0.11_37") (pintype "bidirectional"))
    )
    (net (code "27") (name "/PPS") (class "Default")
      (node (ref "J403") (pin "6") (pinfunction "1PPS_6") (pintype "bidirectional"))
      (node (ref "U401") (pin "46") (pinfunction "(EINT0/MAT0.2/CAP0.2)P0.16_46") (pintype "bidirectional"))
    )
    (net (code "28") (name "/RESET") (class "Default")
      (node (ref "J401") (pin "3") (pinfunction "3_3") (pintype "passive"))
      (node (ref "J402") (pin "3") (pinfunction "3_3") (pintype "passive"))
      (node (ref "R400") (pin "8") (pinfunction "2_8") (pintype "passive"))
      (node (ref "U401") (pin "57") (pinfunction "RESET_57") (pintype "input"))
    )
    (net (code "29") (name "/ROW00") (class "Default")
      (node (ref "D00") (pin "A") (pinfunction "A_A") (pintype "passive"))
      (node (ref "D01") (pin "A") (pinfunction "A_A") (pintype "passive"))
      (node (ref "D02") (pin "A") (pinfunction "A_A") (pintype "passive"))
      (node (ref "D03") (pin "A") (pinfunction "A_A") (pintype "passive"))
      (node (ref "D04") (pin "A") (pinfunction "A_A") (pintype "passive"))
      (node (ref "D05") (pin "A") (pinfunction "A_A") (pintype "passive"))
      (node (ref "D06") (pin "A") (pinfunction "A_A") (pintype "passive"))
      (node (ref "D07") (pin "A") (pinfunction "A_A") (pintype "passive"))
      (node (ref "D08") (pin "A") (pinfunction "A_A") (pintype "passive"))
      (node (ref "D09") (pin "A") (pinfunction "A_A") (pintype "passive"))
      (node (ref "R101") (pin "8") (pinfunction "2_8") (pintype "passive"))
    )
    (net (code "30") (name "/ROW00C") (class "Default")
      (node (ref "R101") (pin "1") (pinfunction "1_1") (pintype "passive"))
      (node (ref "U101") (pin "14") (pinfunction "SEG6/SCL/SCK/RC3_14") (pintype "bidirectional"))
    )
    (net (code "31") (name "/ROW10") (class "Default")
      (node (ref "D10") (pin "A") (pinfunction "A_A") (pintype "passive"))
      (node (ref "D11") (pin "A") (pinfunction "A_A") (pintype "passive"))
      (node (ref "D12") (pin "A") (pinfunction "A_A") (pintype "passive"))
      (node (ref "D13") (pin "A") (pinfunction "A_A") (pintype "passive"))
      (node (ref "D14") (pin "A") (pinfunction "A_A") (pintype "passive"))
      (node (ref "D15") (pin "A") (pinfunction "A_A") (pintype "passive"))
      (node (ref "D16") (pin "A") (pinfunction "A_A") (pintype "passive"))
      (node (ref "D17") (pin "A") (pinfunction "A_A") (pintype "passive"))
      (node (ref "D18") (pin "A") (pinfunction "A_A") (pintype "passive"))
      (node (ref "D19") (pin "A") (pinfunction "A_A") (pintype "passive"))
      (node (ref "R101") (pin "7") (pinfunction "2_7") (pintype "passive"))
    )
    (net (code "32") (name "/ROW10C") (class "Default")
      (node (ref "R101") (pin "2") (pinfunction "1_2") (pintype "passive"))
      (node (ref "U101") (pin "13") (pinfunction "SEG3/P1A/CCP1/RC2_13") (pintype "bidirectional"))
    )
    (net (code "33") (name "/ROW20") (class "Default")
      (node (ref "D20") (pin "A") (pinfunction "A_A") (pintype "passive"))
      (node (ref "D21") (pin "A") (pinfunction "A_A") (pintype "passive"))
      (node (ref "D22") (pin "A") (pinfunction "A_A") (pintype "passive"))
      (node (ref "D23") (pin "A") (pinfunction "A_A") (pintype "passive"))
      (node (ref "D24") (pin "A") (pinfunction "A_A") (pintype "passive"))
      (node (ref "D25") (pin "A") (pinfunction "A_A") (pintype "passive"))
      (node (ref "D26") (pin "A") (pinfunction "A_A") (pintype "passive"))
      (node (ref "D27") (pin "A") (pinfunction "A_A") (pintype "passive"))
      (node (ref "D28") (pin "A") (pinfunction "A_A") (pintype "passive"))
      (node (ref "D29") (pin "A") (pinfunction "A_A") (pintype "passive"))
      (node (ref "R101") (pin "6") (pinfunction "2_6") (pintype "passive"))
    )
    (net (code "34") (name "/ROW20C") (class "Default")
      (node (ref "R101") (pin "3") (pinfunction "1_3") (pintype "passive"))
      (node (ref "U101") (pin "12") (pinfunction "P2A/CCP2/T1OSI/RC1_12") (pintype "bidirectional"))
    )
    (net (code "35") (name "/ROW30") (class "Default")
      (node (ref "D30") (pin "A") (pinfunction "A_A") (pintype "passive"))
      (node (ref "D31") (pin "A") (pinfunction "A_A") (pintype "passive"))
      (node (ref "D32") (pin "A") (pinfunction "A_A") (pintype "passive"))
      (node (ref "D33") (pin "A") (pinfunction "A_A") (pintype "passive"))
      (node (ref "D34") (pin "A") (pinfunction "A_A") (pintype "passive"))
      (node (ref "D35") (pin "A") (pinfunction "A_A") (pintype "passive"))
      (node (ref "D36") (pin "A") (pinfunction "A_A") (pintype "passive"))
      (node (ref "D37") (pin "A") (pinfunction "A_A") (pintype "passive"))
      (node (ref "D38") (pin "A") (pinfunction "A_A") (pintype "passive"))
      (node (ref "D39") (pin "A") (pinfunction "A_A") (pintype "passive"))
      (node (ref "R102") (pin "7") (pinfunction "2_7") (pintype "passive"))
    )
    (net (code "36") (name "/ROW30C") (class "Default")
      (node (ref "R102") (pin "2") (pinfunction "1_2") (pintype "passive"))
      (node (ref "U101") (pin "9") (pinfunction "SEG2/CLKIN/OSC1/RA7_9") (pintype "bidirectional"))
    )
    (net (code "37") (name "/ROW40") (class "Default")
      (node (ref "D40") (pin "A") (pinfunction "A_A") (pintype "passive"))
      (node (ref "D41") (pin "A") (pinfunction "A_A") (pintype "passive"))
      (node (ref "D42") (pin "A") (pinfunction "A_A") (pintype "passive"))
      (node (ref "D43") (pin "A") (pinfunction "A_A") (pintype "passive"))
      (node (ref "D44") (pin "A") (pinfunction "A_A") (pintype "passive"))
      (node (ref "D45") (pin "A") (pinfunction "A_A") (pintype "passive"))
      (node (ref "D46") (pin "A") (pinfunction "A_A") (pintype "passive"))
      (node (ref "D47") (pin "A") (pinfunction "A_A") (pintype "passive"))
      (node (ref "D48") (pin "A") (pinfunction "A_A") (pintype "passive"))
      (node (ref "D49") (pin "A") (pinfunction "A_A") (pintype "passive"))
      (node (ref "R102") (pin "8") (pinfunction "2_8") (pintype "passive"))
    )
    (net (code "38") (name "/ROW40C") (class "Default")
      (node (ref "R102") (pin "1") (pinfunction "1_1") (pintype "passive"))
      (node (ref "U101") (pin "10") (pinfunction "SEG1/VCAP/CLKOUT/OSC2/RA6_10") (pintype "bidirectional"))
    )
    (net (code "39") (name "/ROW50") (class "Default")
      (node (ref "D50") (pin "A") (pinfunction "A_A") (pintype "passive"))
      (node (ref "D51") (pin "A") (pinfunction "A_A") (pintype "passive"))
      (node (ref "D52") (pin "A") (pinfunction "A_A") (pintype "passive"))
      (node (ref "D53") (pin "A") (pinfunction "A_A") (pintype "passive"))
      (node (ref "D54") (pin "A") (pinfunction "A_A") (pintype "passive"))
      (node (ref "D55") (pin "A") (pinfunction "A_A") (pintype "passive"))
      (node (ref "D56") (pin "A") (pinfunction "A_A") (pintype "passive"))
      (node (ref "D57") (pin "A") (pinfunction "A_A") (pintype "passive"))
      (node (ref "D58") (pin "A") (pinfunction "A_A") (pintype "passive"))
      (node (ref "D59") (pin "A") (pinfunction "A_A") (pintype "passive"))
      (node (ref "R101") (pin "5") (pinfunction "2_5") (pintype "passive"))
    )
    (net (code "40") (name "/ROW50C") (class "Default")
      (node (ref "R101") (pin "4") (pinfunction "1_4") (pintype "passive"))
      (node (ref "U101") (pin "11") (pinfunction "P2B/T1CKI/T1OSO/RC0_11") (pintype "bidirectional"))
    )
    (net (code "41") (name "/RX0") (class "Default")
      (node (ref "J401") (pin "2") (pinfunction "2_2") (pintype "passive"))
      (node (ref "J402") (pin "2") (pinfunction "2_2") (pintype "passive"))
      (node (ref "J403") (pin "4") (pinfunction "TX_4") (pintype "bidirectional"))
      (node (ref "U401") (pin "21") (pinfunction "(RXD0/PWM3/EINT0)P0.1_21") (pintype "bidirectional"))
    )
    (net (code "42") (name "/RX1") (class "Default")
      (node (ref "J401") (pin "11") (pinfunction "11_11") (pintype "passive"))
      (node (ref "J402") (pin "11") (pinfunction "11_11") (pintype "passive"))
      (node (ref "U401") (pin "34") (pinfunction "(RXD1/PWM6/EINT3)P0.9_34") (pintype "bidirectional"))
    )
    (net (code "43") (name "/SCK0") (class "Default")
      (node (ref "J701") (pin "5") (pinfunction "SCK_5") (pintype "bidirectional"))
      (node (ref "U401") (pin "27") (pinfunction "(SCK0/CAP0.1/AD0.6)P0.4_27") (pintype "bidirectional"))
    )
    (net (code "44") (name "/S_RST") (class "Default")
      (node (ref "J101") (pin "6") (pinfunction "6_6") (pintype "passive"))
      (node (ref "J102") (pin "6") (pinfunction "6_6") (pintype "passive"))
      (node (ref "SJ6") (pin "3") (pinfunction "3_3") (pintype "passive"))
      (node (ref "U401") (pin "47") (pinfunction "(CAP1.2/SCK1/MAT1.2)P0.17_47") (pintype "bidirectional"))
    )
    (net (code "45") (name "/S_TICK") (class "Default")
      (node (ref "J101") (pin "7") (pinfunction "7_7") (pintype "passive"))
      (node (ref "J102") (pin "7") (pinfunction "7_7") (pintype "passive"))
      (node (ref "SJ5") (pin "3") (pinfunction "3_3") (pintype "passive"))
      (node (ref "U401") (pin "53") (pinfunction "(CAP1.3/MISO1/MAT1.3)P0.18_53") (pintype "bidirectional"))
    )
    (net (code "46") (name "/TX0") (class "Default")
      (node (ref "J401") (pin "1") (pinfunction "1_1") (pintype "passive"))
      (node (ref "J402") (pin "1") (pinfunction "1_1") (pintype "passive"))
      (node (ref "J403") (pin "3") (pinfunction "RX_3") (pintype "bidirectional"))
      (node (ref "U401") (pin "19") (pinfunction "(TXD0/PWM1)P0.0_19") (pintype "bidirectional"))
    )
    (net (code "47") (name "/TX1") (class "Default")
      (node (ref "J401") (pin "10") (pinfunction "10_10") (pintype "passive"))
      (node (ref "J402") (pin "10") (pinfunction "10_10") (pintype "passive"))
      (node (ref "U401") (pin "33") (pinfunction "(TXD1/PWM4/A1.1)P0.8_33") (pintype "bidirectional"))
    )
    (net (code "48") (name "/T_RST") (class "Default")
      (node (ref "J101") (pin "4") (pinfunction "4_4") (pintype "passive"))
      (node (ref "J102") (pin "4") (pinfunction "4_4") (pintype "passive"))
      (node (ref "SJ8") (pin "3") (pinfunction "3_3") (pintype "passive"))
    )
    (net (code "49") (name "/T_TICK") (class "Default")
      (node (ref "J101") (pin "5") (pinfunction "5_5") (pintype "passive"))
      (node (ref "J102") (pin "5") (pinfunction "5_5") (pintype "passive"))
      (node (ref "SJ7") (pin "3") (pinfunction "3_3") (pintype "passive"))
    )
    (net (code "50") (name "/USBCONN_D+") (class "Default")
      (node (ref "J401") (pin "5") (pinfunction "5_5") (pintype "passive"))
      (node (ref "J402") (pin "5") (pinfunction "5_5") (pintype "passive"))
      (node (ref "R030") (pin "2") (pinfunction "2_2") (pintype "passive"))
      (node (ref "R031") (pin "2") (pinfunction "2_2") (pintype "passive"))
    )
    (net (code "51") (name "/USBCONN_D-") (class "Default")
      (node (ref "J401") (pin "7") (pinfunction "7_7") (pintype "passive"))
      (node (ref "J402") (pin "7") (pinfunction "7_7") (pintype "passive"))
      (node (ref "R020") (pin "2") (pinfunction "2_2") (pintype "passive"))
    )
    (net (code "52") (name "/USBD+") (class "Default")
      (node (ref "C030") (pin "1") (pinfunction "1_1") (pintype "passive"))
      (node (ref "R030") (pin "1") (pinfunction "1_1") (pintype "passive"))
      (node (ref "U401") (pin "10") (pinfunction "(AD0.5)P0.26_10") (pintype "bidirectional"))
    )
    (net (code "53") (name "/USBD-") (class "Default")
      (node (ref "C020") (pin "1") (pinfunction "1_1") (pintype "passive"))
      (node (ref "R020") (pin "1") (pinfunction "1_1") (pintype "passive"))
      (node (ref "U401") (pin "11") (pinfunction "(AD0.0/CAP0.1/MAT0.1)P0.27_11") (pintype "bidirectional"))
    )
    (net (code "54") (name "/USB_ON") (class "Default")
      (node (ref "R400") (pin "3") (pinfunction "1_3") (pintype "passive"))
      (node (ref "U401") (pin "58") (pinfunction "P0.23_58") (pintype "bidirectional"))
    )
    (net (code "55") (name "/USB_SOFTCONNECT") (class "Default")
      (node (ref "Q002") (pin "1") (pinfunction "G_1") (pintype "passive"))
      (node (ref "R400") (pin "5") (pinfunction "2_5") (pintype "passive"))
      (node (ref "U401") (pin "17") (pinfunction "P0.31_17") (pintype "output"))
    )
    (net (code "56") (name "/VBUS") (class "Default")
      (node (ref "C010") (pin "1") (pinfunction "1_1") (pintype "passive"))
      (node (ref "C120") (pin "2") (pinfunction "2_2") (pintype "passive"))
      (node (ref "C201") (pin "1") (pinfunction "1_1") (pintype "passive"))
      (node (ref "J401") (pin "8") (pinfunction "8_8") (pintype "passive"))
      (node (ref "J402") (pin "8") (pinfunction "8_8") (pintype "passive"))
      (node (ref "J403") (pin "2") (pinfunction "VCC_2") (pintype "bidirectional"))
      (node (ref "R011") (pin "2") (pinfunction "2_2") (pintype "passive"))
      (node (ref "R400") (pin "6") (pinfunction "2_6") (pintype "passive"))
      (node (ref "SJ9") (pin "1") (pinfunction "1_1") (pintype "passive"))
      (node (ref "U101") (pin "20") (pinfunction "VDD_20") (pintype "power_in"))
      (node (ref "U201") (pin "1") (pinfunction "EN_1") (pintype "input"))
      (node (ref "U201") (pin "2") (pinfunction "IN_2") (pintype "input"))
    )
    (net (code "57") (name "/XTAL1") (class "Default")
      (node (ref "C462") (pin "2") (pinfunction "2_2") (pintype "passive"))
      (node (ref "U401") (pin "62") (pinfunction "XTAL1_62") (pintype "input"))
      (node (ref "Y1") (pin "3") (pinfunction "2_3") (pintype "passive"))
    )
    (net (code "58") (name "/XTAL2") (class "Default")
      (node (ref "C461") (pin "2") (pinfunction "2_2") (pintype "passive"))
      (node (ref "U401") (pin "61") (pinfunction "XTAL2_61") (pintype "output"))
      (node (ref "Y1") (pin "1") (pinfunction "1_1") (pintype "passive"))
    )
    (net (code "59") (name "GND") (class "Default")
      (node (ref "C010") (pin "2") (pinfunction "2_2") (pintype "passive"))
      (node (ref "C020") (pin "2") (pinfunction "2_2") (pintype "passive"))
      (node (ref "C030") (pin "2") (pinfunction "2_2") (pintype "passive"))
      (node (ref "C120") (pin "1") (pinfunction "1_1") (pintype "passive"))
      (node (ref "C201") (pin "2") (pinfunction "2_2") (pintype "passive"))
      (node (ref "C202") (pin "C") (pinfunction "-_C") (pintype "passive"))
      (node (ref "C203") (pin "2") (pinfunction "2_2") (pintype "passive"))
      (node (ref "C407") (pin "2") (pinfunction "2_2") (pintype "passive"))
      (node (ref "C423") (pin "2") (pinfunction "2_2") (pintype "passive"))
      (node (ref "C443") (pin "2") (pinfunction "2_2") (pintype "passive"))
      (node (ref "C451") (pin "2") (pinfunction "2_2") (pintype "passive"))
      (node (ref "C461") (pin "1") (pinfunction "1_1") (pintype "passive"))
      (node (ref "C462") (pin "1") (pinfunction "1_1") (pintype "passive"))
      (node (ref "C701") (pin "2") (pinfunction "2_2") (pintype "passive"))
      (node (ref "J401") (pin "9") (pinfunction "9_9") (pintype "passive"))
      (node (ref "J402") (pin "9") (pinfunction "9_9") (pintype "passive"))
      (node (ref "J403") (pin "1") (pinfunction "GND1_1") (pintype "bidirectional"))
      (node (ref "J403") (pin "5") (pinfunction "GND2_5") (pintype "bidirectional"))
      (node (ref "J701") (pin "6") (pinfunction "GND_6") (pintype "bidirectional"))
      (node (ref "J701") (pin "CD2") (pinfunction "SHIELD_CD2") (pintype "bidirectional"))
      (node (ref "J701") (pin "GND1") (pinfunction "SHIELD_GND1") (pintype "bidirectional"))
      (node (ref "R011") (pin "1") (pinfunction "1_1") (pintype "passive"))
      (node (ref "SJ1") (pin "1") (pinfunction "1_1") (pintype "passive"))
      (node (ref "SJ10") (pin "1") (pinfunction "1_1") (pintype "passive"))
      (node (ref "SJ11") (pin "1") (pinfunction "1_1") (pintype "passive"))
      (node (ref "SJ2") (pin "1") (pinfunction "1_1") (pintype "passive"))
      (node (ref "SJ3") (pin "1") (pinfunction "1_1") (pintype "passive"))
      (node (ref "SJ4") (pin "1") (pinfunction "1_1") (pintype "passive"))
      (node (ref "SJ5") (pin "1") (pinfunction "1_1") (pintype "passive"))
      (node (ref "SJ6") (pin "1") (pinfunction "1_1") (pintype "passive"))
      (node (ref "SJ7") (pin "1") (pinfunction "1_1") (pintype "passive"))
      (node (ref "SJ8") (pin "1") (pinfunction "1_1") (pintype "passive"))
      (node (ref "U101") (pin "19") (pinfunction "VSS_19") (pintype "power_in"))
      (node (ref "U101") (pin "8") (pinfunction "VSS_8") (pintype "power_in"))
      (node (ref "U201") (pin "5") (pinfunction "GND_5") (pintype "power_in"))
      (node (ref "U201") (pin "6") (pinfunction "GND_6") (pintype "power_in"))
      (node (ref "U201") (pin "7") (pinfunction "GND_7") (pintype "power_in"))
      (node (ref "U201") (pin "8") (pinfunction "GND_8") (pintype "power_in"))
      (node (ref "U401") (pin "18") (pinfunction "VSS_18") (pintype "power_in"))
      (node (ref "U401") (pin "25") (pinfunction "VSS_25") (pintype "power_in"))
      (node (ref "U401") (pin "42") (pinfunction "VSS_42") (pintype "power_in"))
      (node (ref "U401") (pin "50") (pinfunction "VSS_50") (pintype "power_in"))
      (node (ref "U401") (pin "59") (pinfunction "VSSA_59") (pintype "power_in"))
      (node (ref "U401") (pin "6") (pinfunction "VSS_6") (pintype "power_in"))
      (node (ref "Y1") (pin "2") (pinfunction "1_2") (pintype "bidirectional"))
      (node (ref "Y1") (pin "4") (pinfunction "1_4") (pintype "bidirectional"))
    )
    (net (code "60") (name "Net-(Q002-D)") (class "Default")
      (node (ref "Q002") (pin "3") (pinfunction "D_3") (pintype "passive"))
      (node (ref "R031") (pin "1") (pinfunction "1_1") (pintype "passive"))
    )
    (net (code "61") (name "Net-(U201A-BYP)") (class "Default")
      (node (ref "C203") (pin "1") (pinfunction "1_1") (pintype "passive"))
      (node (ref "U201") (pin "4") (pinfunction "BYP_4") (pintype "passive"))
    )
    (net (code "62") (name "VCC") (class "Default")
      (node (ref "C202") (pin "A") (pinfunction "+_A") (pintype "passive"))
      (node (ref "C407") (pin "1") (pinfunction "1_1") (pintype "passive"))
      (node (ref "C423") (pin "1") (pinfunction "1_1") (pintype "passive"))
      (node (ref "C443") (pin "1") (pinfunction "1_1") (pintype "passive"))
      (node (ref "C451") (pin "1") (pinfunction "1_1") (pintype "passive"))
      (node (ref "C701") (pin "1") (pinfunction "1_1") (pintype "passive"))
      (node (ref "J401") (pin "6") (pinfunction "6_6") (pintype "passive"))
      (node (ref "J402") (pin "6") (pinfunction "6_6") (pintype "passive"))
      (node (ref "J701") (pin "4") (pinfunction "VCC_4") (pintype "bidirectional"))
      (node (ref "Q002") (pin "2") (pinfunction "S_2") (pintype "passive"))
      (node (ref "R400") (pin "1") (pinfunction "1_1") (pintype "passive"))
      (node (ref "R400") (pin "2") (pinfunction "1_2") (pintype "passive"))
      (node (ref "R400") (pin "4") (pinfunction "1_4") (pintype "passive"))
      (node (ref "U201") (pin "3") (pinfunction "OUT_3") (pintype "output"))
      (node (ref "U401") (pin "23") (pinfunction "VDD3-1_23") (pintype "power_in"))
      (node (ref "U401") (pin "3") (pinfunction "RTXC1_3") (pintype "input"))
      (node (ref "U401") (pin "43") (pinfunction "VDD3-2_43") (pintype "power_in"))
      (node (ref "U401") (pin "49") (pinfunction "VBAT_49") (pintype "power_in"))
      (node (ref "U401") (pin "51") (pinfunction "VDD3-3_51") (pintype "power_in"))
      (node (ref "U401") (pin "63") (pinfunction "VREF_63") (pintype "input"))
      (node (ref "U401") (pin "7") (pinfunction "VDDA3_7") (pintype "power_in"))
    )
    (net (code "63") (name "unconnected-(J701-NC-Pad1)") (class "Default")
      (node (ref "J701") (pin "1") (pinfunction "NC_1") (pintype "bidirectional"))
    )
    (net (code "64") (name "unconnected-(J701-RSV-Pad8)") (class "Default")
      (node (ref "J701") (pin "8") (pinfunction "RSV_8") (pintype "bidirectional"))
    )
    (net (code "65") (name "unconnected-(J701-SHIELD-PadCD1)") (class "Default")
      (node (ref "J701") (pin "CD1") (pinfunction "SHIELD_CD1") (pintype "bidirectional"))
    )
    (net (code "66") (name "unconnected-(J701-SHIELD-PadGND3)") (class "Default")
      (node (ref "J701") (pin "GND3") (pinfunction "SHIELD_GND3") (pintype "bidirectional"))
    )
    (net (code "67") (name "unconnected-(U101-COM2{slash}DACOUT{slash}VREF-{slash}C2IN+{slash}AN2{slash}RA2-Pad4)") (class "Default")
      (node (ref "U101") (pin "4") (pinfunction "COM2/DACOUT/VREF-/C2IN+/AN2/RA2_4") (pintype "bidirectional"))
    )
    (net (code "68") (name "unconnected-(U101-SEG7{slash}C12IN1-{slash}AN1{slash}RA1-Pad3)") (class "Default")
      (node (ref "U101") (pin "3") (pinfunction "SEG7/C12IN1-/AN1/RA1_3") (pintype "bidirectional"))
    )
    (net (code "69") (name "unconnected-(U101-SEG12{slash}VCAP{slash}SS{slash}SRNQ{slash}C2OUT{slash}C12IN0-{slash}AN0{slash}RA0-Pad2)") (class "Default")
      (node (ref "U101") (pin "2") (pinfunction "SEG12/VCAP/SS/SRNQ/C2OUT/C12IN0-/AN0/RA0_2") (pintype "bidirectional"))
    )
    (net (code "70") (name "unconnected-(U101-SEG15{slash}COM3{slash}VREF+{slash}C1IN+{slash}AN3{slash}RA3-Pad5)") (class "Default")
      (node (ref "U101") (pin "5") (pinfunction "SEG15/COM3/VREF+/C1IN+/AN3/RA3_5") (pintype "bidirectional"))
    )
    (net (code "71") (name "unconnected-(U401-(AD0.1{slash}CAP0.2{slash}MAT0.2)P0.28-Pad13)") (class "Default")
      (node (ref "U401") (pin "13") (pinfunction "(AD0.1/CAP0.2/MAT0.2)P0.28_13") (pintype "bidirectional"))
    )
    (net (code "72") (name "unconnected-(U401-(AD0.2{slash}CAP0.3{slash}MAT0.3)P0.29-Pad14)") (class "Default")
      (node (ref "U401") (pin "14") (pinfunction "(AD0.2/CAP0.3/MAT0.3)P0.29_14") (pintype "bidirectional"))
    )
    (net (code "73") (name "unconnected-(U401-(AD0.3{slash}EINT3{slash}CAP0.0)P0.30-Pad15)") (class "Default")
      (node (ref "U401") (pin "15") (pinfunction "(AD0.3/EINT3/CAP0.0)P0.30_15") (pintype "bidirectional"))
    )
    (net (code "74") (name "unconnected-(U401-(AD0.4{slash}AOUT)P0.25-Pad9)") (class "Default")
      (node (ref "U401") (pin "9") (pinfunction "(AD0.4/AOUT)P0.25_9") (pintype "bidirectional"))
    )
    (net (code "75") (name "unconnected-(U401-(AD1.7{slash}CAP0.0{slash}MAT0.0)P0.22-Pad2)") (class "Default")
      (node (ref "U401") (pin "2") (pinfunction "(AD1.7/CAP0.0/MAT0.0)P0.22_2") (pintype "bidirectional"))
    )
    (net (code "76") (name "unconnected-(U401-(MAT1.2{slash}MOSI1{slash}CAP1.2)P0.19-Pad54)") (class "Default")
      (node (ref "U401") (pin "54") (pinfunction "(MAT1.2/MOSI1/CAP1.2)P0.19_54") (pintype "bidirectional"))
    )
    (net (code "77") (name "unconnected-(U401-(MAT1.3{slash}SSEL1{slash}EINT3)P0.20-Pad55)") (class "Default")
      (node (ref "U401") (pin "55") (pinfunction "(MAT1.3/SSEL1/EINT3)P0.20_55") (pintype "bidirectional"))
    )
    (net (code "78") (name "unconnected-(U401-(PWM5{slash}AD1.6{slash}CAP1.3)P0.21-Pad1)") (class "Default")
      (node (ref "U401") (pin "1") (pinfunction "(PWM5/AD1.6/CAP1.3)P0.21_1") (pintype "bidirectional"))
    )
    (net (code "79") (name "unconnected-(U401-(RI1{slash}EINT2{slash}AD1.5)P0.15-Pad45)") (class "Default")
      (node (ref "U401") (pin "45") (pinfunction "(RI1/EINT2/AD1.5)P0.15_45") (pintype "bidirectional"))
    )
    (net (code "80") (name "unconnected-(U401-(SCL0{slash}CAP0.0)P0.2-Pad22)") (class "Default")
      (node (ref "U401") (pin "22") (pinfunction "(SCL0/CAP0.0)P0.2_22") (pintype "bidirectional"))
    )
    (net (code "81") (name "unconnected-(U401-(SDA0{slash}MAT0.0{slash}EINT1)P0.3-Pad26)") (class "Default")
      (node (ref "U401") (pin "26") (pinfunction "(SDA0/MAT0.0/EINT1)P0.3_26") (pintype "bidirectional"))
    )
    (net (code "82") (name "unconnected-(U401-P1.16(TRACEPKT0)-Pad16)") (class "Default")
      (node (ref "U401") (pin "16") (pinfunction "P1.16(TRACEPKT0)_16") (pintype "bidirectional"))
    )
    (net (code "83") (name "unconnected-(U401-P1.17(TRACEPKT1)-Pad12)") (class "Default")
      (node (ref "U401") (pin "12") (pinfunction "P1.17(TRACEPKT1)_12") (pintype "bidirectional"))
    )
    (net (code "84") (name "unconnected-(U401-P1.18(TRACEPKT2)-Pad8)") (class "Default")
      (node (ref "U401") (pin "8") (pinfunction "P1.18(TRACEPKT2)_8") (pintype "bidirectional"))
    )
    (net (code "85") (name "unconnected-(U401-P1.19(TRACEPKT3)-Pad4)") (class "Default")
      (node (ref "U401") (pin "4") (pinfunction "P1.19(TRACEPKT3)_4") (pintype "bidirectional"))
    )
    (net (code "86") (name "unconnected-(U401-P1.20(TRACESYNC)-Pad48)") (class "Default")
      (node (ref "U401") (pin "48") (pinfunction "P1.20(TRACESYNC)_48") (pintype "bidirectional"))
    )
    (net (code "87") (name "unconnected-(U401-P1.21(PIPESTAT0)-Pad44)") (class "Default")
      (node (ref "U401") (pin "44") (pinfunction "P1.21(PIPESTAT0)_44") (pintype "bidirectional"))
    )
    (net (code "88") (name "unconnected-(U401-P1.22(PIPESTAT1)-Pad40)") (class "Default")
      (node (ref "U401") (pin "40") (pinfunction "P1.22(PIPESTAT1)_40") (pintype "bidirectional"))
    )
    (net (code "89") (name "unconnected-(U401-P1.23(PIPESTAT2)-Pad36)") (class "Default")
      (node (ref "U401") (pin "36") (pinfunction "P1.23(PIPESTAT2)_36") (pintype "bidirectional"))
    )
    (net (code "90") (name "unconnected-(U401-P1.24(TRACECLK)-Pad32)") (class "Default")
      (node (ref "U401") (pin "32") (pinfunction "P1.24(TRACECLK)_32") (pintype "bidirectional"))
    )
    (net (code "91") (name "unconnected-(U401-P1.25(EXTIN0)-Pad28)") (class "Default")
      (node (ref "U401") (pin "28") (pinfunction "P1.25(EXTIN0)_28") (pintype "bidirectional"))
    )
    (net (code "92") (name "unconnected-(U401-P1.26(RTCK)-Pad24)") (class "Default")
      (node (ref "U401") (pin "24") (pinfunction "P1.26(RTCK)_24") (pintype "bidirectional"))
    )
    (net (code "93") (name "unconnected-(U401-P1.27(TDO)-Pad64)") (class "Default")
      (node (ref "U401") (pin "64") (pinfunction "P1.27(TDO)_64") (pintype "bidirectional"))
    )
    (net (code "94") (name "unconnected-(U401-P1.28(TDI)-Pad60)") (class "Default")
      (node (ref "U401") (pin "60") (pinfunction "P1.28(TDI)_60") (pintype "bidirectional"))
    )
    (net (code "95") (name "unconnected-(U401-P1.29(TCK)-Pad56)") (class "Default")
      (node (ref "U401") (pin "56") (pinfunction "P1.29(TCK)_56") (pintype "bidirectional"))
    )
    (net (code "96") (name "unconnected-(U401-P1.30(TMS)-Pad52)") (class "Default")
      (node (ref "U401") (pin "52") (pinfunction "P1.30(TMS)_52") (pintype "bidirectional"))
    )
    (net (code "97") (name "unconnected-(U401-P1.31({slash}TRST)-Pad20)") (class "Default")
      (node (ref "U401") (pin "20") (pinfunction "P1.31(/TRST)_20") (pintype "bidirectional"))
    )
    (net (code "98") (name "unconnected-(U401-RTXC2-Pad5)") (class "Default")
      (node (ref "U401") (pin "5") (pinfunction "RTXC2_5") (pintype "output"))
    )
  )
)
